# spino_board.net
KiCad netlist of a schematic drawn in EAGLE
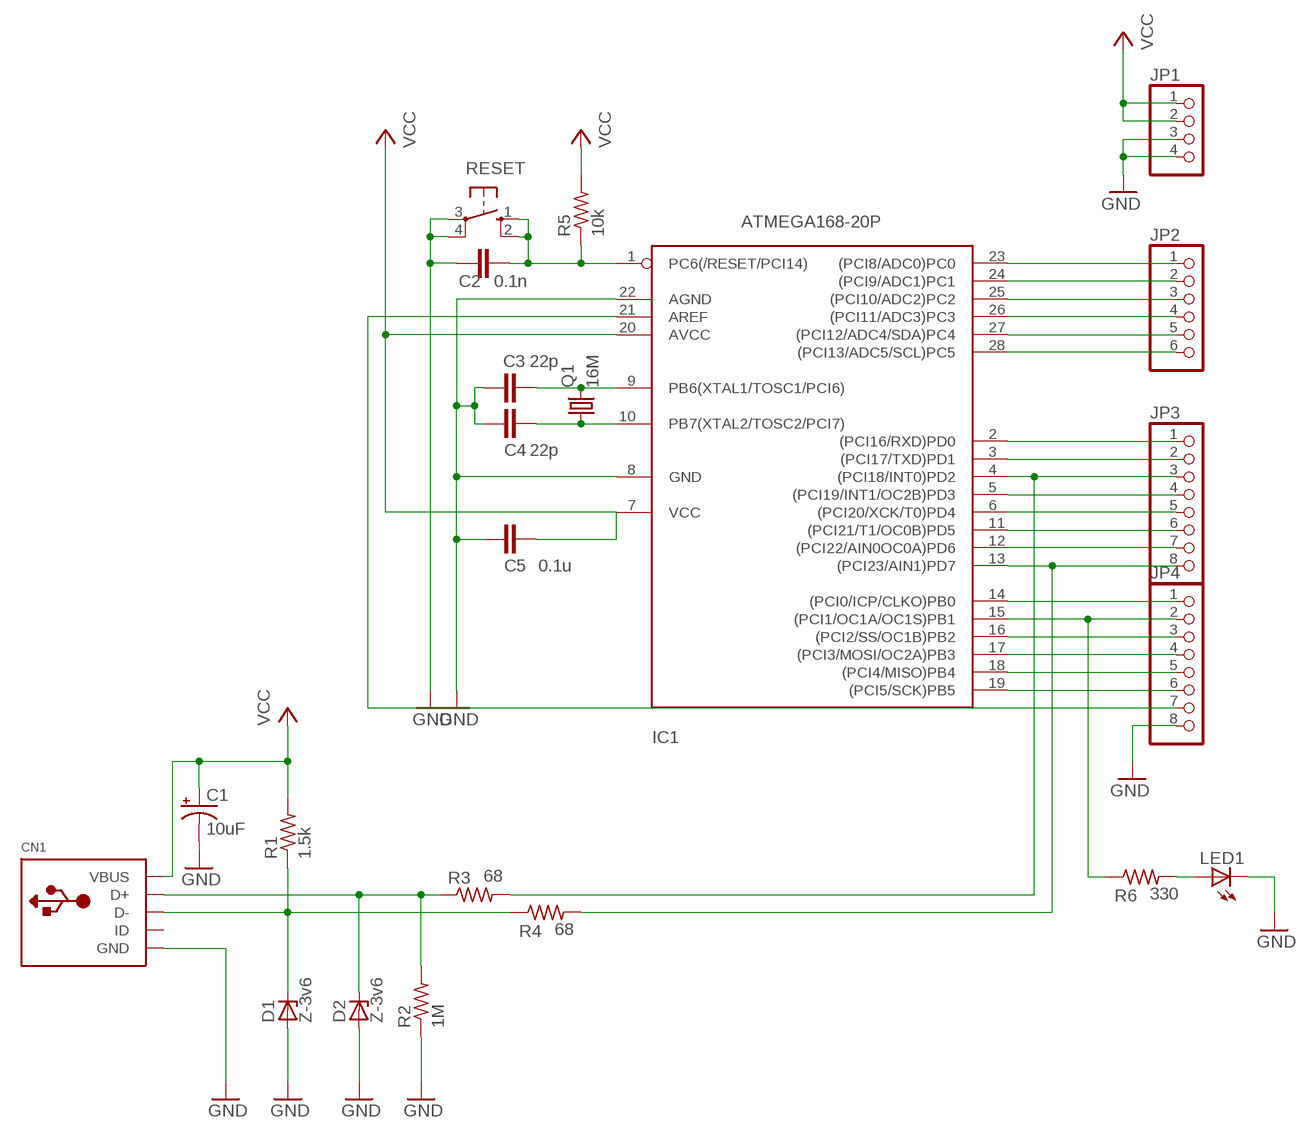
[diagram p0: schematic, sheet 1]

(export (version "E")
  (design (tool "Eeschema 10.0.6"))
  (components
    (comp (ref "C1")
      (value "10uF")
      (footprint "eagle-import:POL-CAP-COMMON")
      (libsource (lib "eagle-import") (part "CPOL-USSANYO_D"))
    )
    (comp (ref "C2")
      (value "0.1n")
      (footprint "eagle-import:C025-060X050")
      (libsource (lib "eagle-import") (part "C-EUCERAMIC-CAP-COMMON"))
    )
    (comp (ref "C3")
      (value "22p")
      (footprint "eagle-import:C025-060X050")
      (libsource (lib "eagle-import") (part "C-EUCERAMIC-CAP-COMMON"))
    )
    (comp (ref "C4")
      (value "22p")
      (footprint "eagle-import:C025-060X050")
      (libsource (lib "eagle-import") (part "C-EUCERAMIC-CAP-COMMON"))
    )
    (comp (ref "C5")
      (value "0.1u")
      (footprint "eagle-import:C025-060X050")
      (libsource (lib "eagle-import") (part "C-EUCERAMIC-CAP-COMMON"))
    )
    (comp (ref "CN1")
      (value "USBMINIB")
      (footprint "eagle-import:USB-MINIB@1")
      (libsource (lib "eagle-import") (part "USBMINIB"))
    )
    (comp (ref "D1")
      (value "Z-3v6")
      (footprint "eagle-import:DO35Z7")
      (libsource (lib "eagle-import") (part "Z-5V1"))
    )
    (comp (ref "D2")
      (value "Z-3v6")
      (footprint "eagle-import:DO35Z7")
      (libsource (lib "eagle-import") (part "Z-5V1"))
    )
    (comp (ref "IC1")
      (value "ATMEGA168-20P")
      (footprint "eagle-import:DIL28-3")
      (libsource (lib "eagle-import") (part "ATMEGA168P-20"))
    )
    (comp (ref "JP1")
      (value "PINHD-1X4")
      (footprint "eagle-import:1X04")
      (libsource (lib "eagle-import") (part "PINHD-1X4"))
    )
    (comp (ref "JP2")
      (value "PINHD-1X6")
      (footprint "eagle-import:1X06")
      (libsource (lib "eagle-import") (part "PINHD-1X6"))
    )
    (comp (ref "JP3")
      (value "PINHD-1X8")
      (footprint "eagle-import:1X08")
      (libsource (lib "eagle-import") (part "PINHD-1X8"))
    )
    (comp (ref "JP4")
      (value "PINHD-1X8")
      (footprint "eagle-import:1X08")
      (libsource (lib "eagle-import") (part "PINHD-1X8"))
    )
    (comp (ref "LED1")
      (value "LED5MM")
      (footprint "eagle-import:LED5MM")
      (libsource (lib "eagle-import") (part "LED5MM"))
    )
    (comp (ref "Q1")
      (value "16M")
      (footprint "eagle-import:HC49_S")
      (libsource (lib "eagle-import") (part "CRYSTALHC49S"))
    )
    (comp (ref "R1")
      (value "1.5k")
      (footprint "eagle-import:R-US-COMMON")
      (libsource (lib "eagle-import") (part "R-US_0207/10"))
    )
    (comp (ref "R2")
      (value "1M")
      (footprint "eagle-import:R-US-COMMON")
      (libsource (lib "eagle-import") (part "R-US_0207/10"))
    )
    (comp (ref "R3")
      (value "68")
      (footprint "eagle-import:R-US-COMMON")
      (libsource (lib "eagle-import") (part "R-US_0207/10"))
    )
    (comp (ref "R4")
      (value "68")
      (footprint "eagle-import:R-US-COMMON")
      (libsource (lib "eagle-import") (part "R-US_0207/10"))
    )
    (comp (ref "R5")
      (value "10k")
      (footprint "eagle-import:R-US-COMMON")
      (libsource (lib "eagle-import") (part "R-US_0207/10"))
    )
    (comp (ref "R6")
      (value "330")
      (footprint "eagle-import:R-US-COMMON")
      (libsource (lib "eagle-import") (part "R-US_0207/10"))
    )
    (comp (ref "RESET")
      (value "10-XX")
      (footprint "eagle-import:B3F-10XX")
      (fields (field (name "MPN") "B3F-1000"))
      (libsource (lib "eagle-import") (part "10-XX"))
    )
  )
  (nets
    (net (code "1") (name "GND") (class "Default")
      (node (ref "C1") (pin "-") (pinfunction "-_-") (pintype "passive"))
      (node (ref "C2") (pin "2") (pinfunction "2_2") (pintype "passive"))
      (node (ref "C3") (pin "2") (pinfunction "2_2") (pintype "passive"))
      (node (ref "C4") (pin "2") (pinfunction "2_2") (pintype "passive"))
      (node (ref "C5") (pin "2") (pinfunction "2_2") (pintype "passive"))
      (node (ref "CN1") (pin "GND") (pinfunction "GND_GND") (pintype "power_in"))
      (node (ref "D1") (pin "A") (pinfunction "A_A") (pintype "passive"))
      (node (ref "D2") (pin "A") (pinfunction "A_A") (pintype "passive"))
      (node (ref "IC1") (pin "22") (pinfunction "AGND_22") (pintype "bidirectional"))
      (node (ref "IC1") (pin "8") (pinfunction "GND_8") (pintype "bidirectional"))
      (node (ref "JP1") (pin "3") (pinfunction "3_3") (pintype "passive"))
      (node (ref "JP1") (pin "4") (pinfunction "4_4") (pintype "passive"))
      (node (ref "JP4") (pin "8") (pinfunction "8_8") (pintype "passive"))
      (node (ref "LED1") (pin "K") (pinfunction "C_K") (pintype "passive"))
      (node (ref "R2") (pin "1") (pinfunction "1_1") (pintype "passive"))
      (node (ref "RESET") (pin "3") (pinfunction "P_3") (pintype "passive"))
      (node (ref "RESET") (pin "4") (pinfunction "P1_4") (pintype "passive"))
    )
    (net (code "2") (name "Net-(CN1-PadD+)") (class "Default")
      (node (ref "CN1") (pin "D+") (pinfunction "D+_D+") (pintype "bidirectional"))
      (node (ref "D2") (pin "C") (pinfunction "C_C") (pintype "passive"))
      (node (ref "R2") (pin "2") (pinfunction "2_2") (pintype "passive"))
      (node (ref "R3") (pin "1") (pinfunction "1_1") (pintype "passive"))
    )
    (net (code "3") (name "Net-(CN1-PadD-)") (class "Default")
      (node (ref "CN1") (pin "D-") (pinfunction "D-_D-") (pintype "bidirectional"))
      (node (ref "D1") (pin "C") (pinfunction "C_C") (pintype "passive"))
      (node (ref "R1") (pin "1") (pinfunction "1_1") (pintype "passive"))
      (node (ref "R4") (pin "1") (pinfunction "1_1") (pintype "passive"))
    )
    (net (code "4") (name "Net-(IC1-(PCI0{slash}ICP{slash}CLKO)PB0)") (class "Default")
      (node (ref "IC1") (pin "14") (pinfunction "(PCI0/ICP/CLKO)PB0_14") (pintype "bidirectional"))
      (node (ref "JP4") (pin "1") (pinfunction "1_1") (pintype "passive"))
    )
    (net (code "5") (name "Net-(IC1-(PCI1{slash}OC1A{slash}OC1S)PB1)") (class "Default")
      (node (ref "IC1") (pin "15") (pinfunction "(PCI1/OC1A/OC1S)PB1_15") (pintype "bidirectional"))
      (node (ref "JP4") (pin "2") (pinfunction "2_2") (pintype "passive"))
      (node (ref "R6") (pin "1") (pinfunction "1_1") (pintype "passive"))
    )
    (net (code "6") (name "Net-(IC1-(PCI2{slash}SS{slash}OC1B)PB2)") (class "Default")
      (node (ref "IC1") (pin "16") (pinfunction "(PCI2/SS/OC1B)PB2_16") (pintype "bidirectional"))
      (node (ref "JP4") (pin "3") (pinfunction "3_3") (pintype "passive"))
    )
    (net (code "7") (name "Net-(IC1-(PCI3{slash}MOSI{slash}OC2A)PB3)") (class "Default")
      (node (ref "IC1") (pin "17") (pinfunction "(PCI3/MOSI/OC2A)PB3_17") (pintype "bidirectional"))
      (node (ref "JP4") (pin "4") (pinfunction "4_4") (pintype "passive"))
    )
    (net (code "8") (name "Net-(IC1-(PCI4{slash}MISO)PB4)") (class "Default")
      (node (ref "IC1") (pin "18") (pinfunction "(PCI4/MISO)PB4_18") (pintype "bidirectional"))
      (node (ref "JP4") (pin "5") (pinfunction "5_5") (pintype "passive"))
    )
    (net (code "9") (name "Net-(IC1-(PCI5{slash}SCK)PB5)") (class "Default")
      (node (ref "IC1") (pin "19") (pinfunction "(PCI5/SCK)PB5_19") (pintype "bidirectional"))
      (node (ref "JP4") (pin "6") (pinfunction "6_6") (pintype "passive"))
    )
    (net (code "10") (name "Net-(IC1-(PCI8{slash}ADC0)PC0)") (class "Default")
      (node (ref "IC1") (pin "23") (pinfunction "(PCI8/ADC0)PC0_23") (pintype "bidirectional"))
      (node (ref "JP2") (pin "1") (pinfunction "1_1") (pintype "passive"))
    )
    (net (code "11") (name "Net-(IC1-(PCI9{slash}ADC1)PC1)") (class "Default")
      (node (ref "IC1") (pin "24") (pinfunction "(PCI9/ADC1)PC1_24") (pintype "bidirectional"))
      (node (ref "JP2") (pin "2") (pinfunction "2_2") (pintype "passive"))
    )
    (net (code "12") (name "Net-(IC1-(PCI10{slash}ADC2)PC2)") (class "Default")
      (node (ref "IC1") (pin "25") (pinfunction "(PCI10/ADC2)PC2_25") (pintype "bidirectional"))
      (node (ref "JP2") (pin "3") (pinfunction "3_3") (pintype "passive"))
    )
    (net (code "13") (name "Net-(IC1-(PCI11{slash}ADC3)PC3)") (class "Default")
      (node (ref "IC1") (pin "26") (pinfunction "(PCI11/ADC3)PC3_26") (pintype "bidirectional"))
      (node (ref "JP2") (pin "4") (pinfunction "4_4") (pintype "passive"))
    )
    (net (code "14") (name "Net-(IC1-(PCI12{slash}ADC4{slash}SDA)PC4)") (class "Default")
      (node (ref "IC1") (pin "27") (pinfunction "(PCI12/ADC4/SDA)PC4_27") (pintype "bidirectional"))
      (node (ref "JP2") (pin "5") (pinfunction "5_5") (pintype "passive"))
    )
    (net (code "15") (name "Net-(IC1-(PCI13{slash}ADC5{slash}SCL)PC5)") (class "Default")
      (node (ref "IC1") (pin "28") (pinfunction "(PCI13/ADC5/SCL)PC5_28") (pintype "bidirectional"))
      (node (ref "JP2") (pin "6") (pinfunction "6_6") (pintype "passive"))
    )
    (net (code "16") (name "Net-(IC1-(PCI16{slash}RXD)PD0)") (class "Default")
      (node (ref "IC1") (pin "2") (pinfunction "(PCI16/RXD)PD0_2") (pintype "bidirectional"))
      (node (ref "JP3") (pin "1") (pinfunction "1_1") (pintype "passive"))
    )
    (net (code "17") (name "Net-(IC1-(PCI17{slash}TXD)PD1)") (class "Default")
      (node (ref "IC1") (pin "3") (pinfunction "(PCI17/TXD)PD1_3") (pintype "bidirectional"))
      (node (ref "JP3") (pin "2") (pinfunction "2_2") (pintype "passive"))
    )
    (net (code "18") (name "Net-(IC1-(PCI18{slash}INT0)PD2)") (class "Default")
      (node (ref "IC1") (pin "4") (pinfunction "(PCI18/INT0)PD2_4") (pintype "bidirectional"))
      (node (ref "JP3") (pin "3") (pinfunction "3_3") (pintype "passive"))
      (node (ref "R3") (pin "2") (pinfunction "2_2") (pintype "passive"))
    )
    (net (code "19") (name "Net-(IC1-(PCI19{slash}INT1{slash}OC2B)PD3)") (class "Default")
      (node (ref "IC1") (pin "5") (pinfunction "(PCI19/INT1/OC2B)PD3_5") (pintype "bidirectional"))
      (node (ref "JP3") (pin "4") (pinfunction "4_4") (pintype "passive"))
    )
    (net (code "20") (name "Net-(IC1-(PCI20{slash}XCK{slash}T0)PD4)") (class "Default")
      (node (ref "IC1") (pin "6") (pinfunction "(PCI20/XCK/T0)PD4_6") (pintype "bidirectional"))
      (node (ref "JP3") (pin "5") (pinfunction "5_5") (pintype "passive"))
    )
    (net (code "21") (name "Net-(IC1-(PCI21{slash}T1{slash}OC0B)PD5)") (class "Default")
      (node (ref "IC1") (pin "11") (pinfunction "(PCI21/T1/OC0B)PD5_11") (pintype "bidirectional"))
      (node (ref "JP3") (pin "6") (pinfunction "6_6") (pintype "passive"))
    )
    (net (code "22") (name "Net-(IC1-(PCI22{slash}AIN0OC0A)PD6)") (class "Default")
      (node (ref "IC1") (pin "12") (pinfunction "(PCI22/AIN0OC0A)PD6_12") (pintype "bidirectional"))
      (node (ref "JP3") (pin "7") (pinfunction "7_7") (pintype "passive"))
    )
    (net (code "23") (name "Net-(IC1-(PCI23{slash}AIN1)PD7)") (class "Default")
      (node (ref "IC1") (pin "13") (pinfunction "(PCI23/AIN1)PD7_13") (pintype "bidirectional"))
      (node (ref "JP3") (pin "8") (pinfunction "8_8") (pintype "passive"))
      (node (ref "R4") (pin "2") (pinfunction "2_2") (pintype "passive"))
    )
    (net (code "24") (name "Net-(IC1-AREF)") (class "Default")
      (node (ref "IC1") (pin "21") (pinfunction "AREF_21") (pintype "bidirectional"))
      (node (ref "JP4") (pin "7") (pinfunction "7_7") (pintype "passive"))
    )
    (net (code "25") (name "Net-(IC1-PB6(XTAL1{slash}TOSC1{slash}PCI6))") (class "Default")
      (node (ref "C3") (pin "1") (pinfunction "1_1") (pintype "passive"))
      (node (ref "IC1") (pin "9") (pinfunction "PB6(XTAL1/TOSC1/PCI6)_9") (pintype "bidirectional"))
      (node (ref "Q1") (pin "2") (pinfunction "2_2") (pintype "passive"))
    )
    (net (code "26") (name "Net-(IC1-PB7(XTAL2{slash}TOSC2{slash}PCI7))") (class "Default")
      (node (ref "C4") (pin "1") (pinfunction "1_1") (pintype "passive"))
      (node (ref "IC1") (pin "10") (pinfunction "PB7(XTAL2/TOSC2/PCI7)_10") (pintype "bidirectional"))
      (node (ref "Q1") (pin "1") (pinfunction "1_1") (pintype "passive"))
    )
    (net (code "27") (name "Net-(IC1-PC6({slash}RESET{slash}PCI14))") (class "Default")
      (node (ref "C2") (pin "1") (pinfunction "1_1") (pintype "passive"))
      (node (ref "IC1") (pin "1") (pinfunction "PC6(/RESET/PCI14)_1") (pintype "bidirectional"))
      (node (ref "R5") (pin "1") (pinfunction "1_1") (pintype "passive"))
      (node (ref "RESET") (pin "1") (pinfunction "S_1") (pintype "passive"))
      (node (ref "RESET") (pin "2") (pinfunction "S1_2") (pintype "passive"))
    )
    (net (code "28") (name "Net-(LED1-PadA)") (class "Default")
      (node (ref "LED1") (pin "A") (pinfunction "A_A") (pintype "passive"))
      (node (ref "R6") (pin "2") (pinfunction "2_2") (pintype "passive"))
    )
    (net (code "29") (name "VCC") (class "Default")
      (node (ref "C1") (pin "+") (pinfunction "+_+") (pintype "passive"))
      (node (ref "C5") (pin "1") (pinfunction "1_1") (pintype "passive"))
      (node (ref "CN1") (pin "VBUS") (pinfunction "VBUS_VBUS") (pintype "power_in"))
      (node (ref "IC1") (pin "20") (pinfunction "AVCC_20") (pintype "bidirectional"))
      (node (ref "IC1") (pin "7") (pinfunction "VCC_7") (pintype "bidirectional"))
      (node (ref "JP1") (pin "1") (pinfunction "1_1") (pintype "passive"))
      (node (ref "JP1") (pin "2") (pinfunction "2_2") (pintype "passive"))
      (node (ref "R1") (pin "2") (pinfunction "2_2") (pintype "passive"))
      (node (ref "R5") (pin "2") (pinfunction "2_2") (pintype "passive"))
    )
    (net (code "30") (name "unconnected-(CN1-PadID)") (class "Default")
      (node (ref "CN1") (pin "ID") (pinfunction "ID_ID") (pintype "bidirectional"))
    )
  )
)
